# Motors.net
KiCad netlist of a schematic drawn in Altium Designer
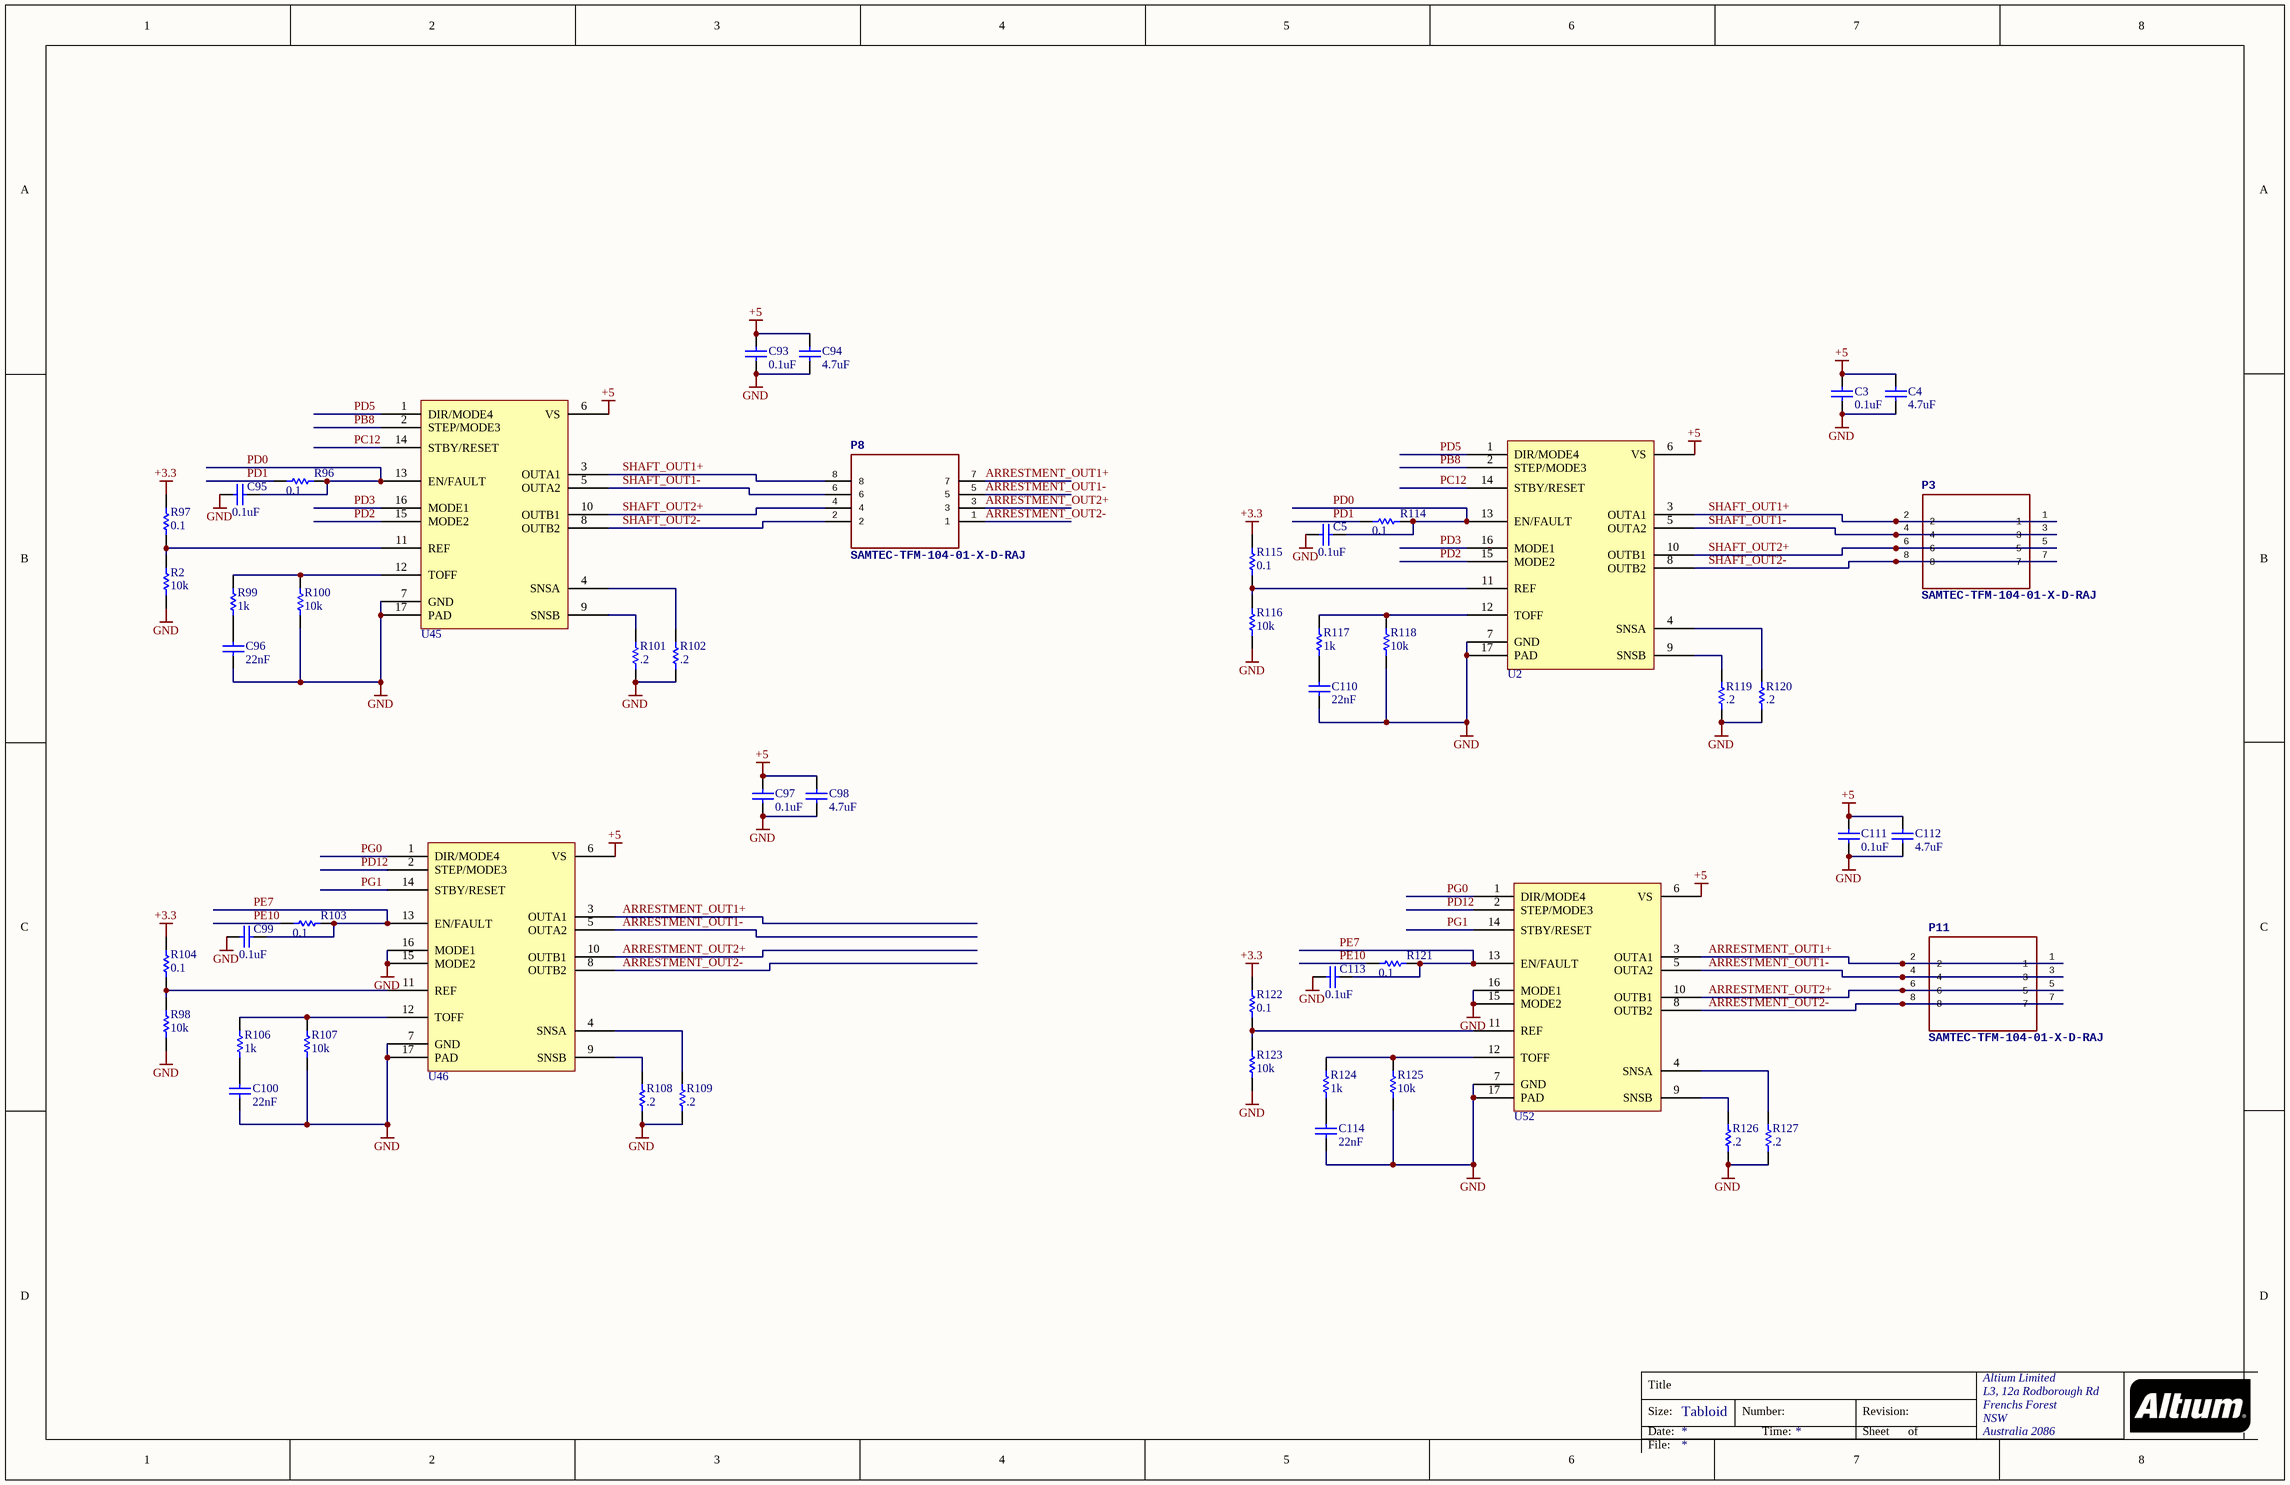
[diagram p0: Motors.SchDoc]

(export (version "E")
  (design (tool "Eeschema 10.0.6"))
  (components
    (comp (ref "C3")
      (value "0.1uF")
      (footprint "CAPC1608X94X35LL15T15")
      (description "CAP .1UF 16V CERAMIC X7R 0603")
      (fields
        (field (name "MANUFACTURER") "Yageo")
        (field (name "MANUFACTURER PART NUMBER") "CC0603KRX7R7BB105")
      )
      (libsource (lib "Altium Content Vault") (part "CAP-NP-2"))
    )
    (comp (ref "C4")
      (value "4.7uF")
      (footprint "CAPC0603(1608)55_M")
      (description "CAP 4.7uF 6.3V ±10% 0603 (1608 Metric) Thickness 0.55mm SMD")
      (fields (field (name "TOLERANCE") "Â±10%") (field (name "MANUFACTURER") "KEMET"))
      (libsource (lib "Altium Content Vault") (part "CAP"))
    )
    (comp (ref "C5")
      (value "0.1uF")
      (footprint "CAPC1608X94X35LL15T15")
      (description "CAP .1UF 16V CERAMIC X7R 0603")
      (fields
        (field (name "MANUFACTURER") "Yageo")
        (field (name "MANUFACTURER PART NUMBER") "CC0603KRX7R7BB105")
      )
      (libsource (lib "Altium Content Vault") (part "CAP-NP-2"))
    )
    (comp (ref "C93")
      (value "0.1uF")
      (footprint "CAPC1608X94X35LL15T15")
      (description "CAP .1UF 16V CERAMIC X7R 0603")
      (fields
        (field (name "MANUFACTURER") "Yageo")
        (field (name "MANUFACTURER PART NUMBER") "CC0603KRX7R7BB105")
      )
      (libsource (lib "Altium Content Vault") (part "CAP-NP-2"))
    )
    (comp (ref "C94")
      (value "4.7uF")
      (footprint "CAPC0603(1608)55_M")
      (description "CAP 4.7uF 6.3V ±10% 0603 (1608 Metric) Thickness 0.55mm SMD")
      (fields (field (name "TOLERANCE") "Â±10%") (field (name "MANUFACTURER") "KEMET"))
      (libsource (lib "Altium Content Vault") (part "CAP"))
    )
    (comp (ref "C95")
      (value "0.1uF")
      (footprint "CAPC1608X94X35LL15T15")
      (description "CAP .1UF 16V CERAMIC X7R 0603")
      (fields
        (field (name "MANUFACTURER") "Yageo")
        (field (name "MANUFACTURER PART NUMBER") "CC0603KRX7R7BB105")
      )
      (libsource (lib "Altium Content Vault") (part "CAP-NP-2"))
    )
    (comp (ref "C96")
      (value "22nF")
      (footprint "CAPC1608X94X35LL15T15")
      (description "CAP .1UF 16V CERAMIC X7R 0603")
      (fields
        (field (name "MANUFACTURER") "Yageo")
        (field (name "MANUFACTURER PART NUMBER") "CC0603KRX7R7BB105")
      )
      (libsource (lib "Altium Content Vault") (part "CMP-1661-00001-2"))
    )
    (comp (ref "C97")
      (value "0.1uF")
      (footprint "CAPC1608X94X35LL15T15")
      (description "CAP .1UF 16V CERAMIC X7R 0603")
      (fields
        (field (name "MANUFACTURER") "Yageo")
        (field (name "MANUFACTURER PART NUMBER") "CC0603KRX7R7BB105")
      )
      (libsource (lib "Altium Content Vault") (part "CAP-NP-2"))
    )
    (comp (ref "C98")
      (value "4.7uF")
      (footprint "CAPC0603(1608)55_M")
      (description "CAP 4.7uF 6.3V ±10% 0603 (1608 Metric) Thickness 0.55mm SMD")
      (fields (field (name "TOLERANCE") "Â±10%") (field (name "MANUFACTURER") "KEMET"))
      (libsource (lib "Altium Content Vault") (part "CAP"))
    )
    (comp (ref "C99")
      (value "0.1uF")
      (footprint "CAPC1608X94X35LL15T15")
      (description "CAP .1UF 16V CERAMIC X7R 0603")
      (fields
        (field (name "MANUFACTURER") "Yageo")
        (field (name "MANUFACTURER PART NUMBER") "CC0603KRX7R7BB105")
      )
      (libsource (lib "Altium Content Vault") (part "CAP-NP-2"))
    )
    (comp (ref "C100")
      (value "22nF")
      (footprint "CAPC1608X94X35LL15T15")
      (description "CAP .1UF 16V CERAMIC X7R 0603")
      (fields
        (field (name "MANUFACTURER") "Yageo")
        (field (name "MANUFACTURER PART NUMBER") "CC0603KRX7R7BB105")
      )
      (libsource (lib "Altium Content Vault") (part "CMP-1661-00001-2"))
    )
    (comp (ref "C110")
      (value "22nF")
      (footprint "CAPC1608X94X35LL15T15")
      (description "CAP .1UF 16V CERAMIC X7R 0603")
      (fields
        (field (name "MANUFACTURER") "Yageo")
        (field (name "MANUFACTURER PART NUMBER") "CC0603KRX7R7BB105")
      )
      (libsource (lib "Altium Content Vault") (part "CMP-1661-00001-2"))
    )
    (comp (ref "C111")
      (value "0.1uF")
      (footprint "CAPC1608X94X35LL15T15")
      (description "CAP .1UF 16V CERAMIC X7R 0603")
      (fields
        (field (name "MANUFACTURER") "Yageo")
        (field (name "MANUFACTURER PART NUMBER") "CC0603KRX7R7BB105")
      )
      (libsource (lib "Altium Content Vault") (part "CAP-NP-2"))
    )
    (comp (ref "C112")
      (value "4.7uF")
      (footprint "CAPC0603(1608)55_M")
      (description "CAP 4.7uF 6.3V ±10% 0603 (1608 Metric) Thickness 0.55mm SMD")
      (fields (field (name "TOLERANCE") "Â±10%") (field (name "MANUFACTURER") "KEMET"))
      (libsource (lib "Altium Content Vault") (part "CAP"))
    )
    (comp (ref "C113")
      (value "0.1uF")
      (footprint "CAPC1608X94X35LL15T15")
      (description "CAP .1UF 16V CERAMIC X7R 0603")
      (fields
        (field (name "MANUFACTURER") "Yageo")
        (field (name "MANUFACTURER PART NUMBER") "CC0603KRX7R7BB105")
      )
      (libsource (lib "Altium Content Vault") (part "CAP-NP-2"))
    )
    (comp (ref "C114")
      (value "22nF")
      (footprint "CAPC1608X94X35LL15T15")
      (description "CAP .1UF 16V CERAMIC X7R 0603")
      (fields
        (field (name "MANUFACTURER") "Yageo")
        (field (name "MANUFACTURER PART NUMBER") "CC0603KRX7R7BB105")
      )
      (libsource (lib "Altium Content Vault") (part "CMP-1661-00001-2"))
    )
    (comp (ref "P3")
      (value "SAMTEC-TFM-104-01-X-D-RAJ")
      (footprint "SAMTEC-TFM-104-01-X-D-RA")
      (libsource (lib "SAMTEC-TFM-104-01-X-D-RA") (part "SAMTEC-TFM-104-01-X-D-RAJ"))
    )
    (comp (ref "P8")
      (value "SAMTEC-TFM-104-01-X-D-RAJ")
      (footprint "SAMTEC-TFM-104-01-X-D-RA")
      (libsource (lib "SAMTEC-TFM-104-01-X-D-RA") (part "SAMTEC-TFM-104-01-X-D-RAJ"))
    )
    (comp (ref "P11")
      (value "SAMTEC-TFM-104-01-X-D-RAJ")
      (footprint "SAMTEC-TFM-104-01-X-D-RA")
      (libsource (lib "SAMTEC-TFM-104-01-X-D-RA") (part "SAMTEC-TFM-104-01-X-D-RAJ"))
    )
    (comp (ref "R2")
      (value "10k")
      (footprint "RESC0603(1608)_N")
      (description "0R12 0.1W 1% 0603 (1608 Metric)  SMD")
      (fields (field (name "POWER") "0.1 W") (field (name "TOLERANCE") "1 %"))
      (libsource (lib "Altium Content Vault") (part "RES"))
    )
    (comp (ref "R96")
      (value "0.1")
      (footprint "RESC0603(1608)_N")
      (description "0R12 0.1W 1% 0603 (1608 Metric)  SMD")
      (fields (field (name "POWER") "0.1 W") (field (name "TOLERANCE") "1 %"))
      (libsource (lib "Altium Content Vault") (part "RES"))
    )
    (comp (ref "R97")
      (value "0.1")
      (footprint "RESC0603(1608)_N")
      (description "0R12 0.1W 1% 0603 (1608 Metric)  SMD")
      (fields (field (name "POWER") "0.1 W") (field (name "TOLERANCE") "1 %"))
      (libsource (lib "Altium Content Vault") (part "RES"))
    )
    (comp (ref "R98")
      (value "10k")
      (footprint "RESC0603(1608)_N")
      (description "0R12 0.1W 1% 0603 (1608 Metric)  SMD")
      (fields (field (name "POWER") "0.1 W") (field (name "TOLERANCE") "1 %"))
      (libsource (lib "Altium Content Vault") (part "RES"))
    )
    (comp (ref "R99")
      (value "1k")
      (footprint "RESC0603(1608)_N")
      (description "0R12 0.1W 1% 0603 (1608 Metric)  SMD")
      (fields (field (name "POWER") "0.1 W") (field (name "TOLERANCE") "1 %"))
      (libsource (lib "Altium Content Vault") (part "RES"))
    )
    (comp (ref "R100")
      (value "10k")
      (footprint "RESC0603(1608)_N")
      (description "0R12 0.1W 1% 0603 (1608 Metric)  SMD")
      (fields (field (name "POWER") "0.1 W") (field (name "TOLERANCE") "1 %"))
      (libsource (lib "Altium Content Vault") (part "RES"))
    )
    (comp (ref "R101")
      (value ".2")
      (footprint "RESC0603(1608)_N")
      (description "0R12 0.1W 1% 0603 (1608 Metric)  SMD")
      (fields (field (name "POWER") "0.1 W") (field (name "TOLERANCE") "1 %"))
      (libsource (lib "Altium Content Vault") (part "CMP-1012-00511-1"))
    )
    (comp (ref "R102")
      (value ".2")
      (footprint "RESC0603(1608)_N")
      (description "0R12 0.1W 1% 0603 (1608 Metric)  SMD")
      (fields (field (name "POWER") "0.1 W") (field (name "TOLERANCE") "1 %"))
      (libsource (lib "Altium Content Vault") (part "RES"))
    )
    (comp (ref "R103")
      (value "0.1")
      (footprint "RESC0603(1608)_N")
      (description "0R12 0.1W 1% 0603 (1608 Metric)  SMD")
      (fields (field (name "POWER") "0.1 W") (field (name "TOLERANCE") "1 %"))
      (libsource (lib "Altium Content Vault") (part "RES"))
    )
    (comp (ref "R104")
      (value "0.1")
      (footprint "RESC0603(1608)_N")
      (description "0R12 0.1W 1% 0603 (1608 Metric)  SMD")
      (fields (field (name "POWER") "0.1 W") (field (name "TOLERANCE") "1 %"))
      (libsource (lib "Altium Content Vault") (part "RES"))
    )
    (comp (ref "R106")
      (value "1k")
      (footprint "RESC0603(1608)_N")
      (description "0R12 0.1W 1% 0603 (1608 Metric)  SMD")
      (fields (field (name "POWER") "0.1 W") (field (name "TOLERANCE") "1 %"))
      (libsource (lib "Altium Content Vault") (part "RES"))
    )
    (comp (ref "R107")
      (value "10k")
      (footprint "RESC0603(1608)_N")
      (description "0R12 0.1W 1% 0603 (1608 Metric)  SMD")
      (fields (field (name "POWER") "0.1 W") (field (name "TOLERANCE") "1 %"))
      (libsource (lib "Altium Content Vault") (part "RES"))
    )
    (comp (ref "R108")
      (value ".2")
      (footprint "RESC0603(1608)_N")
      (description "0R12 0.1W 1% 0603 (1608 Metric)  SMD")
      (fields (field (name "POWER") "0.1 W") (field (name "TOLERANCE") "1 %"))
      (libsource (lib "Altium Content Vault") (part "CMP-1012-00511-1"))
    )
    (comp (ref "R109")
      (value ".2")
      (footprint "RESC0603(1608)_N")
      (description "0R12 0.1W 1% 0603 (1608 Metric)  SMD")
      (fields (field (name "POWER") "0.1 W") (field (name "TOLERANCE") "1 %"))
      (libsource (lib "Altium Content Vault") (part "RES"))
    )
    (comp (ref "R114")
      (value "0.1")
      (footprint "RESC0603(1608)_N")
      (description "0R12 0.1W 1% 0603 (1608 Metric)  SMD")
      (fields (field (name "POWER") "0.1 W") (field (name "TOLERANCE") "1 %"))
      (libsource (lib "Altium Content Vault") (part "RES"))
    )
    (comp (ref "R115")
      (value "0.1")
      (footprint "RESC0603(1608)_N")
      (description "0R12 0.1W 1% 0603 (1608 Metric)  SMD")
      (fields (field (name "POWER") "0.1 W") (field (name "TOLERANCE") "1 %"))
      (libsource (lib "Altium Content Vault") (part "RES"))
    )
    (comp (ref "R116")
      (value "10k")
      (footprint "RESC0603(1608)_N")
      (description "0R12 0.1W 1% 0603 (1608 Metric)  SMD")
      (fields (field (name "POWER") "0.1 W") (field (name "TOLERANCE") "1 %"))
      (libsource (lib "Altium Content Vault") (part "RES"))
    )
    (comp (ref "R117")
      (value "1k")
      (footprint "RESC0603(1608)_N")
      (description "0R12 0.1W 1% 0603 (1608 Metric)  SMD")
      (fields (field (name "POWER") "0.1 W") (field (name "TOLERANCE") "1 %"))
      (libsource (lib "Altium Content Vault") (part "RES"))
    )
    (comp (ref "R118")
      (value "10k")
      (footprint "RESC0603(1608)_N")
      (description "0R12 0.1W 1% 0603 (1608 Metric)  SMD")
      (fields (field (name "POWER") "0.1 W") (field (name "TOLERANCE") "1 %"))
      (libsource (lib "Altium Content Vault") (part "RES"))
    )
    (comp (ref "R119")
      (value ".2")
      (footprint "RESC0603(1608)_N")
      (description "0R12 0.1W 1% 0603 (1608 Metric)  SMD")
      (fields (field (name "POWER") "0.1 W") (field (name "TOLERANCE") "1 %"))
      (libsource (lib "Altium Content Vault") (part "CMP-1012-00511-1"))
    )
    (comp (ref "R120")
      (value ".2")
      (footprint "RESC0603(1608)_N")
      (description "0R12 0.1W 1% 0603 (1608 Metric)  SMD")
      (fields (field (name "POWER") "0.1 W") (field (name "TOLERANCE") "1 %"))
      (libsource (lib "Altium Content Vault") (part "RES"))
    )
    (comp (ref "R121")
      (value "0.1")
      (footprint "RESC0603(1608)_N")
      (description "0R12 0.1W 1% 0603 (1608 Metric)  SMD")
      (fields (field (name "POWER") "0.1 W") (field (name "TOLERANCE") "1 %"))
      (libsource (lib "Altium Content Vault") (part "RES"))
    )
    (comp (ref "R122")
      (value "0.1")
      (footprint "RESC0603(1608)_N")
      (description "0R12 0.1W 1% 0603 (1608 Metric)  SMD")
      (fields (field (name "POWER") "0.1 W") (field (name "TOLERANCE") "1 %"))
      (libsource (lib "Altium Content Vault") (part "RES"))
    )
    (comp (ref "R123")
      (value "10k")
      (footprint "RESC0603(1608)_N")
      (description "0R12 0.1W 1% 0603 (1608 Metric)  SMD")
      (fields (field (name "POWER") "0.1 W") (field (name "TOLERANCE") "1 %"))
      (libsource (lib "Altium Content Vault") (part "RES"))
    )
    (comp (ref "R124")
      (value "1k")
      (footprint "RESC0603(1608)_N")
      (description "0R12 0.1W 1% 0603 (1608 Metric)  SMD")
      (fields (field (name "POWER") "0.1 W") (field (name "TOLERANCE") "1 %"))
      (libsource (lib "Altium Content Vault") (part "RES"))
    )
    (comp (ref "R125")
      (value "10k")
      (footprint "RESC0603(1608)_N")
      (description "0R12 0.1W 1% 0603 (1608 Metric)  SMD")
      (fields (field (name "POWER") "0.1 W") (field (name "TOLERANCE") "1 %"))
      (libsource (lib "Altium Content Vault") (part "RES"))
    )
    (comp (ref "R126")
      (value ".2")
      (footprint "RESC0603(1608)_N")
      (description "0R12 0.1W 1% 0603 (1608 Metric)  SMD")
      (fields (field (name "POWER") "0.1 W") (field (name "TOLERANCE") "1 %"))
      (libsource (lib "Altium Content Vault") (part "CMP-1012-00511-1"))
    )
    (comp (ref "R127")
      (value ".2")
      (footprint "RESC0603(1608)_N")
      (description "0R12 0.1W 1% 0603 (1608 Metric)  SMD")
      (fields (field (name "POWER") "0.1 W") (field (name "TOLERANCE") "1 %"))
      (libsource (lib "Altium Content Vault") (part "RES"))
    )
    (comp (ref "U2")
      (value "STSPIN220")
      (footprint "STSPIN220-QFN127P600-8N")
      (libsource (lib "ZLS_Schematic_lib") (part "STSPIN220"))
    )
    (comp (ref "U45")
      (value "STSPIN220")
      (footprint "STSPIN220-QFN127P600-8N")
      (libsource (lib "ZLS_Schematic_lib") (part "STSPIN220"))
    )
    (comp (ref "U46")
      (value "STSPIN220")
      (footprint "STSPIN220-QFN127P600-8N")
      (libsource (lib "ZLS_Schematic_lib") (part "STSPIN220"))
    )
    (comp (ref "U52")
      (value "STSPIN220")
      (footprint "STSPIN220-QFN127P600-8N")
      (libsource (lib "ZLS_Schematic_lib") (part "STSPIN220"))
    )
  )
  (nets
    (net (code "1") (name "+3.3") (class "Default")
      (node (ref "R104") (pin "2") (pinfunction "2_2") (pintype "passive"))
      (node (ref "R115") (pin "2") (pinfunction "2_2") (pintype "passive"))
      (node (ref "R122") (pin "2") (pinfunction "2_2") (pintype "passive"))
      (node (ref "R97") (pin "2") (pinfunction "2_2") (pintype "passive"))
    )
    (net (code "2") (name "+5") (class "Default")
      (node (ref "C111") (pin "1") (pinfunction "1_1") (pintype "passive"))
      (node (ref "C112") (pin "2") (pinfunction "2_2") (pintype "passive"))
      (node (ref "C3") (pin "1") (pinfunction "1_1") (pintype "passive"))
      (node (ref "C4") (pin "2") (pinfunction "2_2") (pintype "passive"))
      (node (ref "C93") (pin "1") (pinfunction "1_1") (pintype "passive"))
      (node (ref "C94") (pin "2") (pinfunction "2_2") (pintype "passive"))
      (node (ref "C97") (pin "1") (pinfunction "1_1") (pintype "passive"))
      (node (ref "C98") (pin "2") (pinfunction "2_2") (pintype "passive"))
      (node (ref "U2") (pin "6") (pinfunction "VS_6") (pintype "passive"))
      (node (ref "U45") (pin "6") (pinfunction "VS_6") (pintype "passive"))
      (node (ref "U46") (pin "6") (pinfunction "VS_6") (pintype "passive"))
      (node (ref "U52") (pin "6") (pinfunction "VS_6") (pintype "passive"))
    )
    (net (code "3") (name "/ARRESTMENT_OUT1+") (class "Default")
      (node (ref "P11") (pin "1") (pinfunction "1_1") (pintype "passive"))
      (node (ref "P11") (pin "2") (pinfunction "2_2") (pintype "passive"))
      (node (ref "P8") (pin "7") (pinfunction "7_7") (pintype "passive"))
      (node (ref "U46") (pin "3") (pinfunction "OUTA1_3") (pintype "passive"))
      (node (ref "U52") (pin "3") (pinfunction "OUTA1_3") (pintype "passive"))
    )
    (net (code "4") (name "/ARRESTMENT_OUT1-") (class "Default")
      (node (ref "P11") (pin "3") (pinfunction "3_3") (pintype "passive"))
      (node (ref "P11") (pin "4") (pinfunction "4_4") (pintype "passive"))
      (node (ref "P8") (pin "5") (pinfunction "5_5") (pintype "passive"))
      (node (ref "U46") (pin "5") (pinfunction "OUTA2_5") (pintype "passive"))
      (node (ref "U52") (pin "5") (pinfunction "OUTA2_5") (pintype "passive"))
    )
    (net (code "5") (name "/ARRESTMENT_OUT2+") (class "Default")
      (node (ref "P11") (pin "5") (pinfunction "5_5") (pintype "passive"))
      (node (ref "P11") (pin "6") (pinfunction "6_6") (pintype "passive"))
      (node (ref "P8") (pin "3") (pinfunction "3_3") (pintype "passive"))
      (node (ref "U46") (pin "10") (pinfunction "OUTB1_10") (pintype "passive"))
      (node (ref "U52") (pin "10") (pinfunction "OUTB1_10") (pintype "passive"))
    )
    (net (code "6") (name "/ARRESTMENT_OUT2-") (class "Default")
      (node (ref "P11") (pin "7") (pinfunction "7_7") (pintype "passive"))
      (node (ref "P11") (pin "8") (pinfunction "8_8") (pintype "passive"))
      (node (ref "P8") (pin "1") (pinfunction "1_1") (pintype "passive"))
      (node (ref "U46") (pin "8") (pinfunction "OUTB2_8") (pintype "passive"))
      (node (ref "U52") (pin "8") (pinfunction "OUTB2_8") (pintype "passive"))
    )
    (net (code "7") (name "/PB8") (class "Default")
      (node (ref "U2") (pin "2") (pinfunction "STEP/MODE3_2") (pintype "passive"))
      (node (ref "U45") (pin "2") (pinfunction "STEP/MODE3_2") (pintype "passive"))
    )
    (net (code "8") (name "/PC12") (class "Default")
      (node (ref "U2") (pin "14") (pinfunction "STBY/RESET_14") (pintype "passive"))
      (node (ref "U45") (pin "14") (pinfunction "STBY/RESET_14") (pintype "passive"))
    )
    (net (code "9") (name "/PD0") (class "Default")
      (node (ref "C5") (pin "2") (pinfunction "2_2") (pintype "passive"))
      (node (ref "C95") (pin "2") (pinfunction "2_2") (pintype "passive"))
      (node (ref "R114") (pin "1") (pinfunction "1_1") (pintype "passive"))
      (node (ref "R96") (pin "1") (pinfunction "1_1") (pintype "passive"))
      (node (ref "U2") (pin "13") (pinfunction "EN/FAULT_13") (pintype "passive"))
      (node (ref "U45") (pin "13") (pinfunction "EN/FAULT_13") (pintype "passive"))
    )
    (net (code "10") (name "/PD1") (class "Default")
      (node (ref "R114") (pin "2") (pinfunction "2_2") (pintype "passive"))
      (node (ref "R96") (pin "2") (pinfunction "2_2") (pintype "passive"))
    )
    (net (code "11") (name "/PD2") (class "Default")
      (node (ref "U2") (pin "15") (pinfunction "MODE2_15") (pintype "passive"))
      (node (ref "U45") (pin "15") (pinfunction "MODE2_15") (pintype "passive"))
    )
    (net (code "12") (name "/PD3") (class "Default")
      (node (ref "U2") (pin "16") (pinfunction "MODE1_16") (pintype "passive"))
      (node (ref "U45") (pin "16") (pinfunction "MODE1_16") (pintype "passive"))
    )
    (net (code "13") (name "/PD5") (class "Default")
      (node (ref "U2") (pin "1") (pinfunction "DIR/MODE4_1") (pintype "passive"))
      (node (ref "U45") (pin "1") (pinfunction "DIR/MODE4_1") (pintype "passive"))
    )
    (net (code "14") (name "/PD12") (class "Default")
      (node (ref "U46") (pin "2") (pinfunction "STEP/MODE3_2") (pintype "passive"))
      (node (ref "U52") (pin "2") (pinfunction "STEP/MODE3_2") (pintype "passive"))
    )
    (net (code "15") (name "/PE7") (class "Default")
      (node (ref "C113") (pin "2") (pinfunction "2_2") (pintype "passive"))
      (node (ref "C99") (pin "2") (pinfunction "2_2") (pintype "passive"))
      (node (ref "R103") (pin "1") (pinfunction "1_1") (pintype "passive"))
      (node (ref "R121") (pin "1") (pinfunction "1_1") (pintype "passive"))
      (node (ref "U46") (pin "13") (pinfunction "EN/FAULT_13") (pintype "passive"))
      (node (ref "U52") (pin "13") (pinfunction "EN/FAULT_13") (pintype "passive"))
    )
    (net (code "16") (name "/PE10") (class "Default")
      (node (ref "R103") (pin "2") (pinfunction "2_2") (pintype "passive"))
      (node (ref "R121") (pin "2") (pinfunction "2_2") (pintype "passive"))
    )
    (net (code "17") (name "/PG0") (class "Default")
      (node (ref "U46") (pin "1") (pinfunction "DIR/MODE4_1") (pintype "passive"))
      (node (ref "U52") (pin "1") (pinfunction "DIR/MODE4_1") (pintype "passive"))
    )
    (net (code "18") (name "/PG1") (class "Default")
      (node (ref "U46") (pin "14") (pinfunction "STBY/RESET_14") (pintype "passive"))
      (node (ref "U52") (pin "14") (pinfunction "STBY/RESET_14") (pintype "passive"))
    )
    (net (code "19") (name "/SHAFT_OUT1+") (class "Default")
      (node (ref "P3") (pin "1") (pinfunction "1_1") (pintype "passive"))
      (node (ref "P3") (pin "2") (pinfunction "2_2") (pintype "passive"))
      (node (ref "P8") (pin "8") (pinfunction "8_8") (pintype "passive"))
      (node (ref "U2") (pin "3") (pinfunction "OUTA1_3") (pintype "passive"))
      (node (ref "U45") (pin "3") (pinfunction "OUTA1_3") (pintype "passive"))
    )
    (net (code "20") (name "/SHAFT_OUT1-") (class "Default")
      (node (ref "P3") (pin "3") (pinfunction "3_3") (pintype "passive"))
      (node (ref "P3") (pin "4") (pinfunction "4_4") (pintype "passive"))
      (node (ref "P8") (pin "6") (pinfunction "6_6") (pintype "passive"))
      (node (ref "U2") (pin "5") (pinfunction "OUTA2_5") (pintype "passive"))
      (node (ref "U45") (pin "5") (pinfunction "OUTA2_5") (pintype "passive"))
    )
    (net (code "21") (name "/SHAFT_OUT2+") (class "Default")
      (node (ref "P3") (pin "5") (pinfunction "5_5") (pintype "passive"))
      (node (ref "P3") (pin "6") (pinfunction "6_6") (pintype "passive"))
      (node (ref "P8") (pin "4") (pinfunction "4_4") (pintype "passive"))
      (node (ref "U2") (pin "10") (pinfunction "OUTB1_10") (pintype "passive"))
      (node (ref "U45") (pin "10") (pinfunction "OUTB1_10") (pintype "passive"))
    )
    (net (code "22") (name "/SHAFT_OUT2-") (class "Default")
      (node (ref "P3") (pin "7") (pinfunction "7_7") (pintype "passive"))
      (node (ref "P3") (pin "8") (pinfunction "8_8") (pintype "passive"))
      (node (ref "P8") (pin "2") (pinfunction "2_2") (pintype "passive"))
      (node (ref "U2") (pin "8") (pinfunction "OUTB2_8") (pintype "passive"))
      (node (ref "U45") (pin "8") (pinfunction "OUTB2_8") (pintype "passive"))
    )
    (net (code "23") (name "GND") (class "Default")
      (node (ref "C100") (pin "2") (pinfunction "2_2") (pintype "passive"))
      (node (ref "C110") (pin "2") (pinfunction "2_2") (pintype "passive"))
      (node (ref "C111") (pin "2") (pinfunction "2_2") (pintype "passive"))
      (node (ref "C112") (pin "1") (pinfunction "1_1") (pintype "passive"))
      (node (ref "C113") (pin "1") (pinfunction "1_1") (pintype "passive"))
      (node (ref "C114") (pin "2") (pinfunction "2_2") (pintype "passive"))
      (node (ref "C3") (pin "2") (pinfunction "2_2") (pintype "passive"))
      (node (ref "C4") (pin "1") (pinfunction "1_1") (pintype "passive"))
      (node (ref "C5") (pin "1") (pinfunction "1_1") (pintype "passive"))
      (node (ref "C93") (pin "2") (pinfunction "2_2") (pintype "passive"))
      (node (ref "C94") (pin "1") (pinfunction "1_1") (pintype "passive"))
      (node (ref "C95") (pin "1") (pinfunction "1_1") (pintype "passive"))
      (node (ref "C96") (pin "2") (pinfunction "2_2") (pintype "passive"))
      (node (ref "C97") (pin "2") (pinfunction "2_2") (pintype "passive"))
      (node (ref "C98") (pin "1") (pinfunction "1_1") (pintype "passive"))
      (node (ref "C99") (pin "1") (pinfunction "1_1") (pintype "passive"))
      (node (ref "R100") (pin "1") (pinfunction "1_1") (pintype "passive"))
      (node (ref "R101") (pin "1") (pinfunction "1_1") (pintype "passive"))
      (node (ref "R102") (pin "1") (pinfunction "1_1") (pintype "passive"))
      (node (ref "R107") (pin "1") (pinfunction "1_1") (pintype "passive"))
      (node (ref "R108") (pin "1") (pinfunction "1_1") (pintype "passive"))
      (node (ref "R109") (pin "1") (pinfunction "1_1") (pintype "passive"))
      (node (ref "R116") (pin "1") (pinfunction "1_1") (pintype "passive"))
      (node (ref "R118") (pin "1") (pinfunction "1_1") (pintype "passive"))
      (node (ref "R119") (pin "1") (pinfunction "1_1") (pintype "passive"))
      (node (ref "R120") (pin "1") (pinfunction "1_1") (pintype "passive"))
      (node (ref "R123") (pin "1") (pinfunction "1_1") (pintype "passive"))
      (node (ref "R125") (pin "1") (pinfunction "1_1") (pintype "passive"))
      (node (ref "R126") (pin "1") (pinfunction "1_1") (pintype "passive"))
      (node (ref "R127") (pin "1") (pinfunction "1_1") (pintype "passive"))
      (node (ref "R2") (pin "1") (pinfunction "1_1") (pintype "passive"))
      (node (ref "R98") (pin "1") (pinfunction "1_1") (pintype "passive"))
      (node (ref "U2") (pin "17") (pinfunction "PAD_17") (pintype "passive"))
      (node (ref "U2") (pin "7") (pinfunction "GND_7") (pintype "passive"))
      (node (ref "U45") (pin "17") (pinfunction "PAD_17") (pintype "passive"))
      (node (ref "U45") (pin "7") (pinfunction "GND_7") (pintype "passive"))
      (node (ref "U46") (pin "15") (pinfunction "MODE2_15") (pintype "passive"))
      (node (ref "U46") (pin "16") (pinfunction "MODE1_16") (pintype "passive"))
      (node (ref "U46") (pin "17") (pinfunction "PAD_17") (pintype "passive"))
      (node (ref "U46") (pin "7") (pinfunction "GND_7") (pintype "passive"))
      (node (ref "U52") (pin "15") (pinfunction "MODE2_15") (pintype "passive"))
      (node (ref "U52") (pin "16") (pinfunction "MODE1_16") (pintype "passive"))
      (node (ref "U52") (pin "17") (pinfunction "PAD_17") (pintype "passive"))
      (node (ref "U52") (pin "7") (pinfunction "GND_7") (pintype "passive"))
    )
    (net (code "24") (name "Net-(C96-Pad1)") (class "Default")
      (node (ref "C96") (pin "1") (pinfunction "1_1") (pintype "passive"))
      (node (ref "R99") (pin "1") (pinfunction "1_1") (pintype "passive"))
    )
    (net (code "25") (name "Net-(C100-Pad1)") (class "Default")
      (node (ref "C100") (pin "1") (pinfunction "1_1") (pintype "passive"))
      (node (ref "R106") (pin "1") (pinfunction "1_1") (pintype "passive"))
    )
    (net (code "26") (name "Net-(C110-Pad1)") (class "Default")
      (node (ref "C110") (pin "1") (pinfunction "1_1") (pintype "passive"))
      (node (ref "R117") (pin "1") (pinfunction "1_1") (pintype "passive"))
    )
    (net (code "27") (name "Net-(C114-Pad1)") (class "Default")
      (node (ref "C114") (pin "1") (pinfunction "1_1") (pintype "passive"))
      (node (ref "R124") (pin "1") (pinfunction "1_1") (pintype "passive"))
    )
    (net (code "28") (name "Net-(U2-REF)") (class "Default")
      (node (ref "R115") (pin "1") (pinfunction "1_1") (pintype "passive"))
      (node (ref "R116") (pin "2") (pinfunction "2_2") (pintype "passive"))
      (node (ref "U2") (pin "11") (pinfunction "REF_11") (pintype "passive"))
    )
    (net (code "29") (name "Net-(U2-SNSA)") (class "Default")
      (node (ref "R120") (pin "2") (pinfunction "2_2") (pintype "passive"))
      (node (ref "U2") (pin "4") (pinfunction "SNSA_4") (pintype "passive"))
    )
    (net (code "30") (name "Net-(U2-SNSB)") (class "Default")
      (node (ref "R119") (pin "2") (pinfunction "2_2") (pintype "passive"))
      (node (ref "U2") (pin "9") (pinfunction "SNSB_9") (pintype "passive"))
    )
    (net (code "31") (name "Net-(U2-TOFF)") (class "Default")
      (node (ref "R117") (pin "2") (pinfunction "2_2") (pintype "passive"))
      (node (ref "R118") (pin "2") (pinfunction "2_2") (pintype "passive"))
      (node (ref "U2") (pin "12") (pinfunction "TOFF_12") (pintype "passive"))
    )
    (net (code "32") (name "Net-(U45-REF)") (class "Default")
      (node (ref "R2") (pin "2") (pinfunction "2_2") (pintype "passive"))
      (node (ref "R97") (pin "1") (pinfunction "1_1") (pintype "passive"))
      (node (ref "U45") (pin "11") (pinfunction "REF_11") (pintype "passive"))
    )
    (net (code "33") (name "Net-(U45-SNSA)") (class "Default")
      (node (ref "R102") (pin "2") (pinfunction "2_2") (pintype "passive"))
      (node (ref "U45") (pin "4") (pinfunction "SNSA_4") (pintype "passive"))
    )
    (net (code "34") (name "Net-(U45-SNSB)") (class "Default")
      (node (ref "R101") (pin "2") (pinfunction "2_2") (pintype "passive"))
      (node (ref "U45") (pin "9") (pinfunction "SNSB_9") (pintype "passive"))
    )
    (net (code "35") (name "Net-(U45-TOFF)") (class "Default")
      (node (ref "R100") (pin "2") (pinfunction "2_2") (pintype "passive"))
      (node (ref "R99") (pin "2") (pinfunction "2_2") (pintype "passive"))
      (node (ref "U45") (pin "12") (pinfunction "TOFF_12") (pintype "passive"))
    )
    (net (code "36") (name "Net-(U46-REF)") (class "Default")
      (node (ref "R104") (pin "1") (pinfunction "1_1") (pintype "passive"))
      (node (ref "R98") (pin "2") (pinfunction "2_2") (pintype "passive"))
      (node (ref "U46") (pin "11") (pinfunction "REF_11") (pintype "passive"))
    )
    (net (code "37") (name "Net-(U46-SNSA)") (class "Default")
      (node (ref "R109") (pin "2") (pinfunction "2_2") (pintype "passive"))
      (node (ref "U46") (pin "4") (pinfunction "SNSA_4") (pintype "passive"))
    )
    (net (code "38") (name "Net-(U46-SNSB)") (class "Default")
      (node (ref "R108") (pin "2") (pinfunction "2_2") (pintype "passive"))
      (node (ref "U46") (pin "9") (pinfunction "SNSB_9") (pintype "passive"))
    )
    (net (code "39") (name "Net-(U46-TOFF)") (class "Default")
      (node (ref "R106") (pin "2") (pinfunction "2_2") (pintype "passive"))
      (node (ref "R107") (pin "2") (pinfunction "2_2") (pintype "passive"))
      (node (ref "U46") (pin "12") (pinfunction "TOFF_12") (pintype "passive"))
    )
    (net (code "40") (name "Net-(U52-REF)") (class "Default")
      (node (ref "R122") (pin "1") (pinfunction "1_1") (pintype "passive"))
      (node (ref "R123") (pin "2") (pinfunction "2_2") (pintype "passive"))
      (node (ref "U52") (pin "11") (pinfunction "REF_11") (pintype "passive"))
    )
    (net (code "41") (name "Net-(U52-SNSA)") (class "Default")
      (node (ref "R127") (pin "2") (pinfunction "2_2") (pintype "passive"))
      (node (ref "U52") (pin "4") (pinfunction "SNSA_4") (pintype "passive"))
    )
    (net (code "42") (name "Net-(U52-SNSB)") (class "Default")
      (node (ref "R126") (pin "2") (pinfunction "2_2") (pintype "passive"))
      (node (ref "U52") (pin "9") (pinfunction "SNSB_9") (pintype "passive"))
    )
    (net (code "43") (name "Net-(U52-TOFF)") (class "Default")
      (node (ref "R124") (pin "2") (pinfunction "2_2") (pintype "passive"))
      (node (ref "R125") (pin "2") (pinfunction "2_2") (pintype "passive"))
      (node (ref "U52") (pin "12") (pinfunction "TOFF_12") (pintype "passive"))
    )
  )
)
